# rapidshark-main-breakout-top-mk-1_10.net
KiCad netlist of a schematic drawn in EAGLE
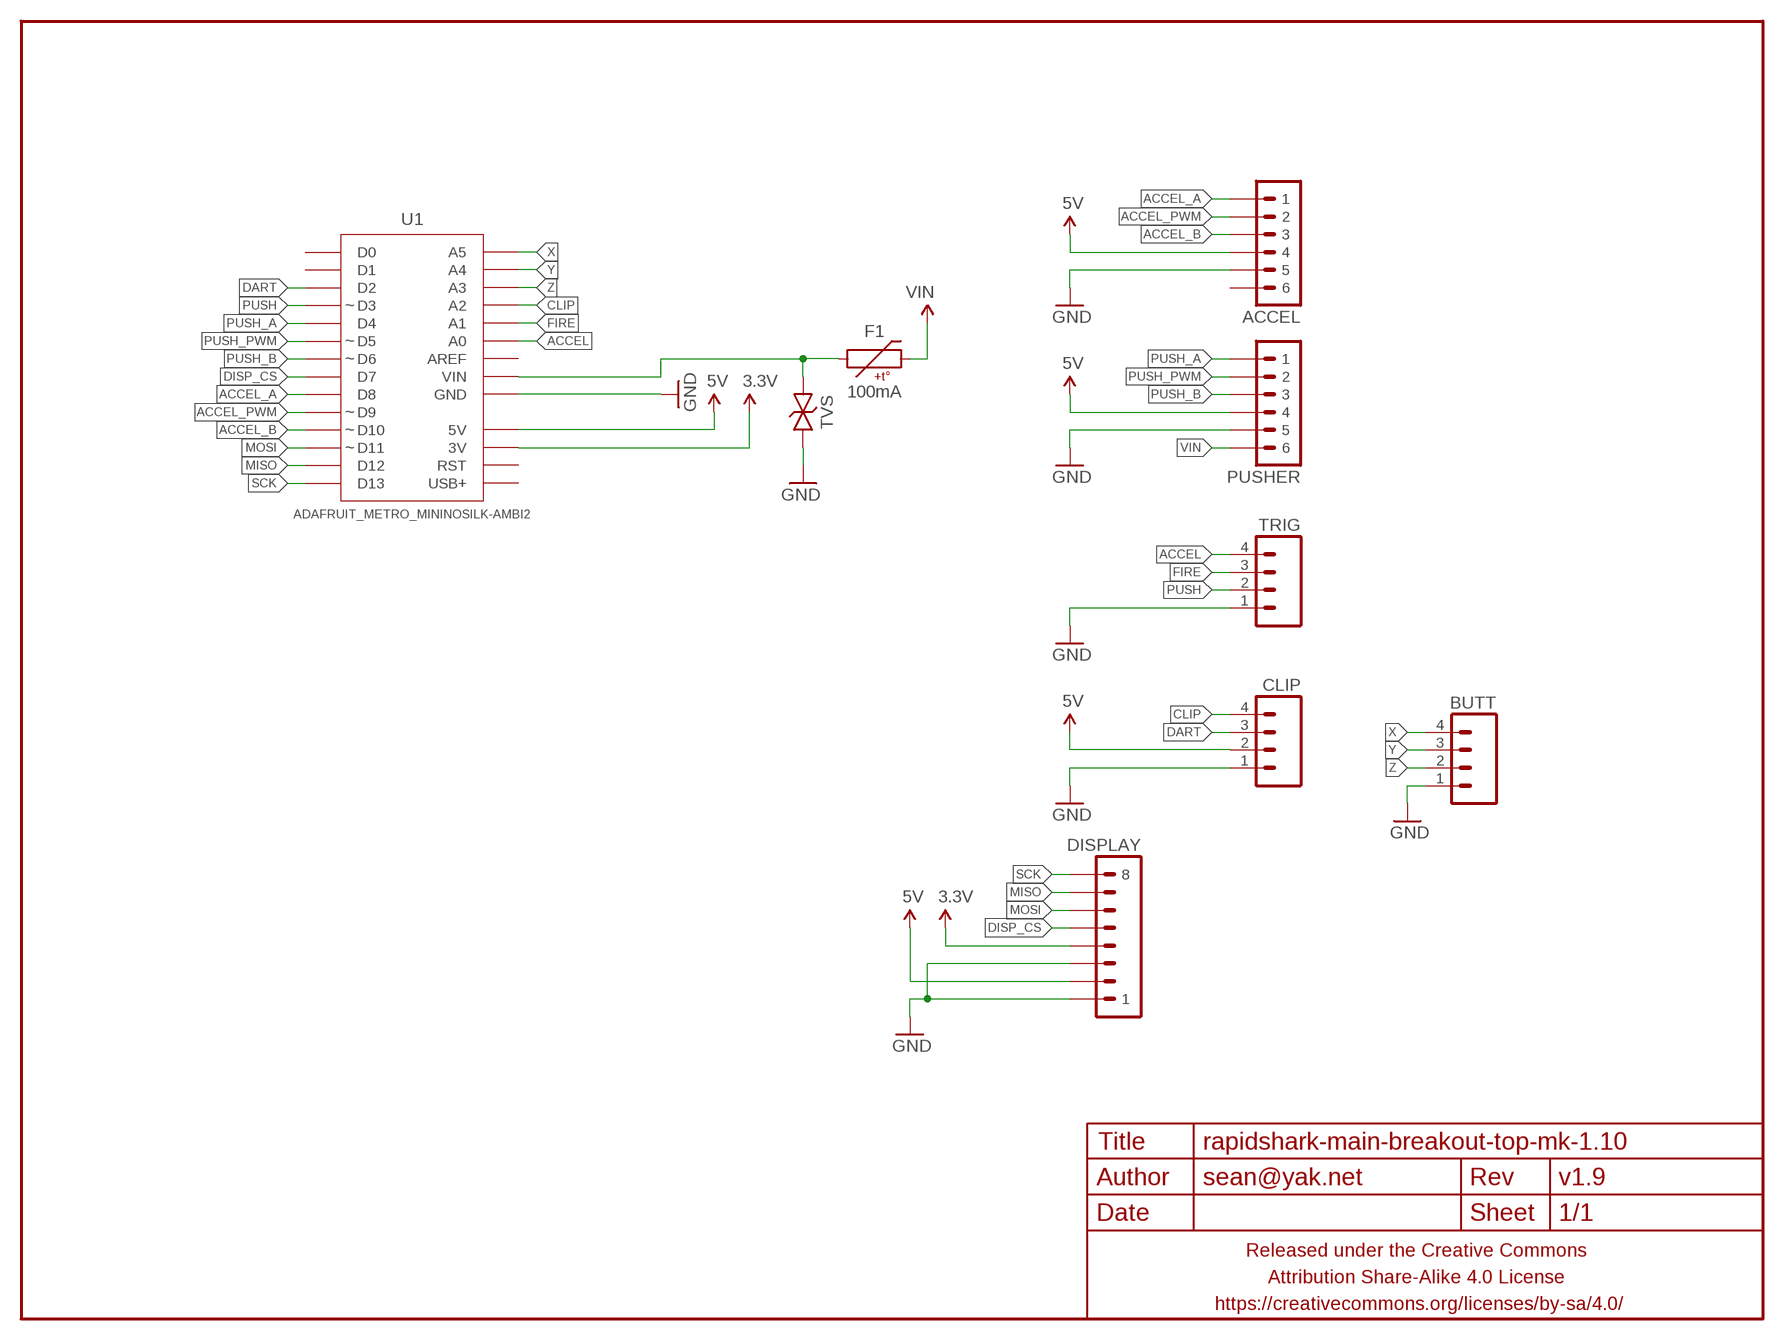
[diagram p0: schematic, sheet 1]

(export (version "E")
  (design (tool "Eeschema 10.0.6"))
  (components
    (comp (ref "ACCEL")
      (value "M06JST-PH-PTH-VERT")
      (footprint "eagle-import:JST-6-PH-VERT-PTH")
      (libsource (lib "eagle-import") (part "M06JST-PH-PTH-VERT"))
    )
    (comp (ref "BUTT")
      (value "M04JST-PTH-VERT")
      (footprint "eagle-import:JST-4-PH-VERT-PTH")
      (libsource (lib "eagle-import") (part "M04JST-PTH-VERT"))
    )
    (comp (ref "CLIP")
      (value "M04JST-PTH-VERT")
      (footprint "eagle-import:JST-4-PH-VERT-PTH")
      (libsource (lib "eagle-import") (part "M04JST-PTH-VERT"))
    )
    (comp (ref "DISPLAY")
      (value "M08JST-PH-VERT-PTH")
      (footprint "eagle-import:JST-8-VERT-PTH")
      (libsource (lib "eagle-import") (part "M08JST-PH-VERT-PTH"))
    )
    (comp (ref "F1")
      (value "100mA")
      (footprint "eagle-import:PTC-1206")
      (libsource (lib "eagle-import") (part "PTCSMD"))
    )
    (comp (ref "FRAME1")
      (value "FRAME-LETTERNO_PACKAGE")
      (footprint "eagle-import:DUMMY")
      (fields (field (name "DESIGNER") "sean@yak.net") (field (name "VERSION") "v1.9"))
      (libsource (lib "eagle-import") (part "FRAME-LETTERNO_PACKAGE"))
    )
    (comp (ref "PUSHER")
      (value "M06JST-PH-PTH-VERT")
      (footprint "eagle-import:JST-6-PH-VERT-PTH")
      (libsource (lib "eagle-import") (part "M06JST-PH-PTH-VERT"))
    )
    (comp (ref "TRIG")
      (value "M04JST-PTH-VERT")
      (footprint "eagle-import:JST-4-PH-VERT-PTH")
      (libsource (lib "eagle-import") (part "M04JST-PTH-VERT"))
    )
    (comp (ref "TVS")
      (value "TVSSMA")
      (footprint "eagle-import:SMA-DIODE-TVS-BIDIR")
      (libsource (lib "eagle-import") (part "TVSSMA"))
    )
    (comp (ref "U1")
      (value "ADAFRUIT_METRO_MININOSILK-AMBI2")
      (footprint "eagle-import:ADAFRUIT_METRO_MINI_BACK")
      (libsource (lib "eagle-import") (part "ADAFRUIT_METRO_MININOSILK-AMBI2"))
    )
  )
  (nets
    (net (code "1") (name "3.3V") (class "Default")
      (node (ref "DISPLAY") (pin "4") (pinfunction "4_4") (pintype "passive"))
      (node (ref "U1") (pin "17") (pinfunction "3V_17") (pintype "bidirectional"))
    )
    (net (code "2") (name "5V") (class "Default")
      (node (ref "ACCEL") (pin "4") (pinfunction "4_4") (pintype "passive"))
      (node (ref "CLIP") (pin "2") (pinfunction "2_2") (pintype "passive"))
      (node (ref "DISPLAY") (pin "2") (pinfunction "2_2") (pintype "passive"))
      (node (ref "PUSHER") (pin "4") (pinfunction "4_4") (pintype "passive"))
      (node (ref "U1") (pin "18") (pinfunction "5V_18") (pintype "bidirectional"))
    )
    (net (code "3") (name "ACCEL") (class "Default")
      (node (ref "TRIG") (pin "4") (pinfunction "4_4") (pintype "passive"))
      (node (ref "U1") (pin "23") (pinfunction "A0_23") (pintype "bidirectional"))
    )
    (net (code "4") (name "ACCEL_A") (class "Default")
      (node (ref "ACCEL") (pin "1") (pinfunction "1_1") (pintype "passive"))
      (node (ref "U1") (pin "9") (pinfunction "D8_9") (pintype "bidirectional"))
    )
    (net (code "5") (name "ACCEL_B") (class "Default")
      (node (ref "ACCEL") (pin "3") (pinfunction "3_3") (pintype "passive"))
      (node (ref "U1") (pin "11") (pinfunction "D10_11") (pintype "bidirectional"))
    )
    (net (code "6") (name "ACCEL_PWM") (class "Default")
      (node (ref "ACCEL") (pin "2") (pinfunction "2_2") (pintype "passive"))
      (node (ref "U1") (pin "10") (pinfunction "D9_10") (pintype "bidirectional"))
    )
    (net (code "7") (name "CLIP") (class "Default")
      (node (ref "CLIP") (pin "4") (pinfunction "4_4") (pintype "passive"))
      (node (ref "U1") (pin "25") (pinfunction "A2_25") (pintype "bidirectional"))
    )
    (net (code "8") (name "DART") (class "Default")
      (node (ref "CLIP") (pin "3") (pinfunction "3_3") (pintype "passive"))
      (node (ref "U1") (pin "3") (pinfunction "D2_3") (pintype "bidirectional"))
    )
    (net (code "9") (name "DISP_CS") (class "Default")
      (node (ref "DISPLAY") (pin "5") (pinfunction "5_5") (pintype "passive"))
      (node (ref "U1") (pin "8") (pinfunction "D7_8") (pintype "bidirectional"))
    )
    (net (code "10") (name "FIRE") (class "Default")
      (node (ref "TRIG") (pin "3") (pinfunction "3_3") (pintype "passive"))
      (node (ref "U1") (pin "24") (pinfunction "A1_24") (pintype "bidirectional"))
    )
    (net (code "11") (name "GND") (class "Default")
      (node (ref "ACCEL") (pin "5") (pinfunction "5_5") (pintype "passive"))
      (node (ref "BUTT") (pin "1") (pinfunction "1_1") (pintype "passive"))
      (node (ref "CLIP") (pin "1") (pinfunction "1_1") (pintype "passive"))
      (node (ref "DISPLAY") (pin "1") (pinfunction "1_1") (pintype "passive"))
      (node (ref "DISPLAY") (pin "3") (pinfunction "3_3") (pintype "passive"))
      (node (ref "PUSHER") (pin "5") (pinfunction "5_5") (pintype "passive"))
      (node (ref "TRIG") (pin "1") (pinfunction "1_1") (pintype "passive"))
      (node (ref "TVS") (pin "1") (pinfunction "1_1") (pintype "passive"))
      (node (ref "U1") (pin "19") (pinfunction "GND_19") (pintype "bidirectional"))
      (node (ref "U1") (pin "20") (pinfunction "GND_20") (pintype "bidirectional"))
    )
    (net (code "12") (name "MISO") (class "Default")
      (node (ref "DISPLAY") (pin "7") (pinfunction "7_7") (pintype "passive"))
      (node (ref "U1") (pin "13") (pinfunction "D12_13") (pintype "bidirectional"))
    )
    (net (code "13") (name "MOSI") (class "Default")
      (node (ref "DISPLAY") (pin "6") (pinfunction "6_6") (pintype "passive"))
      (node (ref "U1") (pin "12") (pinfunction "D11_12") (pintype "bidirectional"))
    )
    (net (code "14") (name "Net-(U1-VIN)") (class "Default")
      (node (ref "F1") (pin "1") (pinfunction "1_1") (pintype "passive"))
      (node (ref "TVS") (pin "2") (pinfunction "2_2") (pintype "passive"))
      (node (ref "U1") (pin "21") (pinfunction "VIN_21") (pintype "bidirectional"))
    )
    (net (code "15") (name "PUSH") (class "Default")
      (node (ref "TRIG") (pin "2") (pinfunction "2_2") (pintype "passive"))
      (node (ref "U1") (pin "4") (pinfunction "D3_4") (pintype "bidirectional"))
    )
    (net (code "16") (name "PUSH_A") (class "Default")
      (node (ref "PUSHER") (pin "1") (pinfunction "1_1") (pintype "passive"))
      (node (ref "U1") (pin "5") (pinfunction "D4_5") (pintype "bidirectional"))
    )
    (net (code "17") (name "PUSH_B") (class "Default")
      (node (ref "PUSHER") (pin "3") (pinfunction "3_3") (pintype "passive"))
      (node (ref "U1") (pin "7") (pinfunction "D6_7") (pintype "bidirectional"))
    )
    (net (code "18") (name "PUSH_PWM") (class "Default")
      (node (ref "PUSHER") (pin "2") (pinfunction "2_2") (pintype "passive"))
      (node (ref "U1") (pin "6") (pinfunction "D5_6") (pintype "bidirectional"))
    )
    (net (code "19") (name "SCK") (class "Default")
      (node (ref "DISPLAY") (pin "8") (pinfunction "8_8") (pintype "passive"))
      (node (ref "U1") (pin "14") (pinfunction "D13_14") (pintype "bidirectional"))
    )
    (net (code "20") (name "VIN") (class "Default")
      (node (ref "F1") (pin "2") (pinfunction "2_2") (pintype "passive"))
      (node (ref "PUSHER") (pin "6") (pinfunction "6_6") (pintype "passive"))
    )
    (net (code "21") (name "X") (class "Default")
      (node (ref "BUTT") (pin "4") (pinfunction "4_4") (pintype "passive"))
      (node (ref "U1") (pin "28") (pinfunction "A5_28") (pintype "bidirectional"))
    )
    (net (code "22") (name "Y") (class "Default")
      (node (ref "BUTT") (pin "3") (pinfunction "3_3") (pintype "passive"))
      (node (ref "U1") (pin "27") (pinfunction "A4_27") (pintype "bidirectional"))
    )
    (net (code "23") (name "Z") (class "Default")
      (node (ref "BUTT") (pin "2") (pinfunction "2_2") (pintype "passive"))
      (node (ref "U1") (pin "26") (pinfunction "A3_26") (pintype "bidirectional"))
    )
    (net (code "24") (name "unconnected-(ACCEL-Pad6)") (class "Default")
      (node (ref "ACCEL") (pin "6") (pinfunction "6_6") (pintype "passive"))
    )
    (net (code "25") (name "unconnected-(U1-AREF-Pad22)") (class "Default")
      (node (ref "U1") (pin "22") (pinfunction "AREF_22") (pintype "bidirectional"))
    )
    (net (code "26") (name "unconnected-(U1-D0-Pad1)") (class "Default")
      (node (ref "U1") (pin "1") (pinfunction "D0_1") (pintype "bidirectional"))
    )
    (net (code "27") (name "unconnected-(U1-D1-Pad2)") (class "Default")
      (node (ref "U1") (pin "2") (pinfunction "D1_2") (pintype "bidirectional"))
    )
    (net (code "28") (name "unconnected-(U1-RST-Pad16)") (class "Default")
      (node (ref "U1") (pin "16") (pinfunction "RST_16") (pintype "bidirectional"))
    )
    (net (code "29") (name "unconnected-(U1-USB+-Pad15)") (class "Default")
      (node (ref "U1") (pin "15") (pinfunction "USB+_15") (pintype "bidirectional"))
    )
  )
)
